# Sch_pwr_sys.net
KiCad netlist of a schematic drawn in Altium Designer
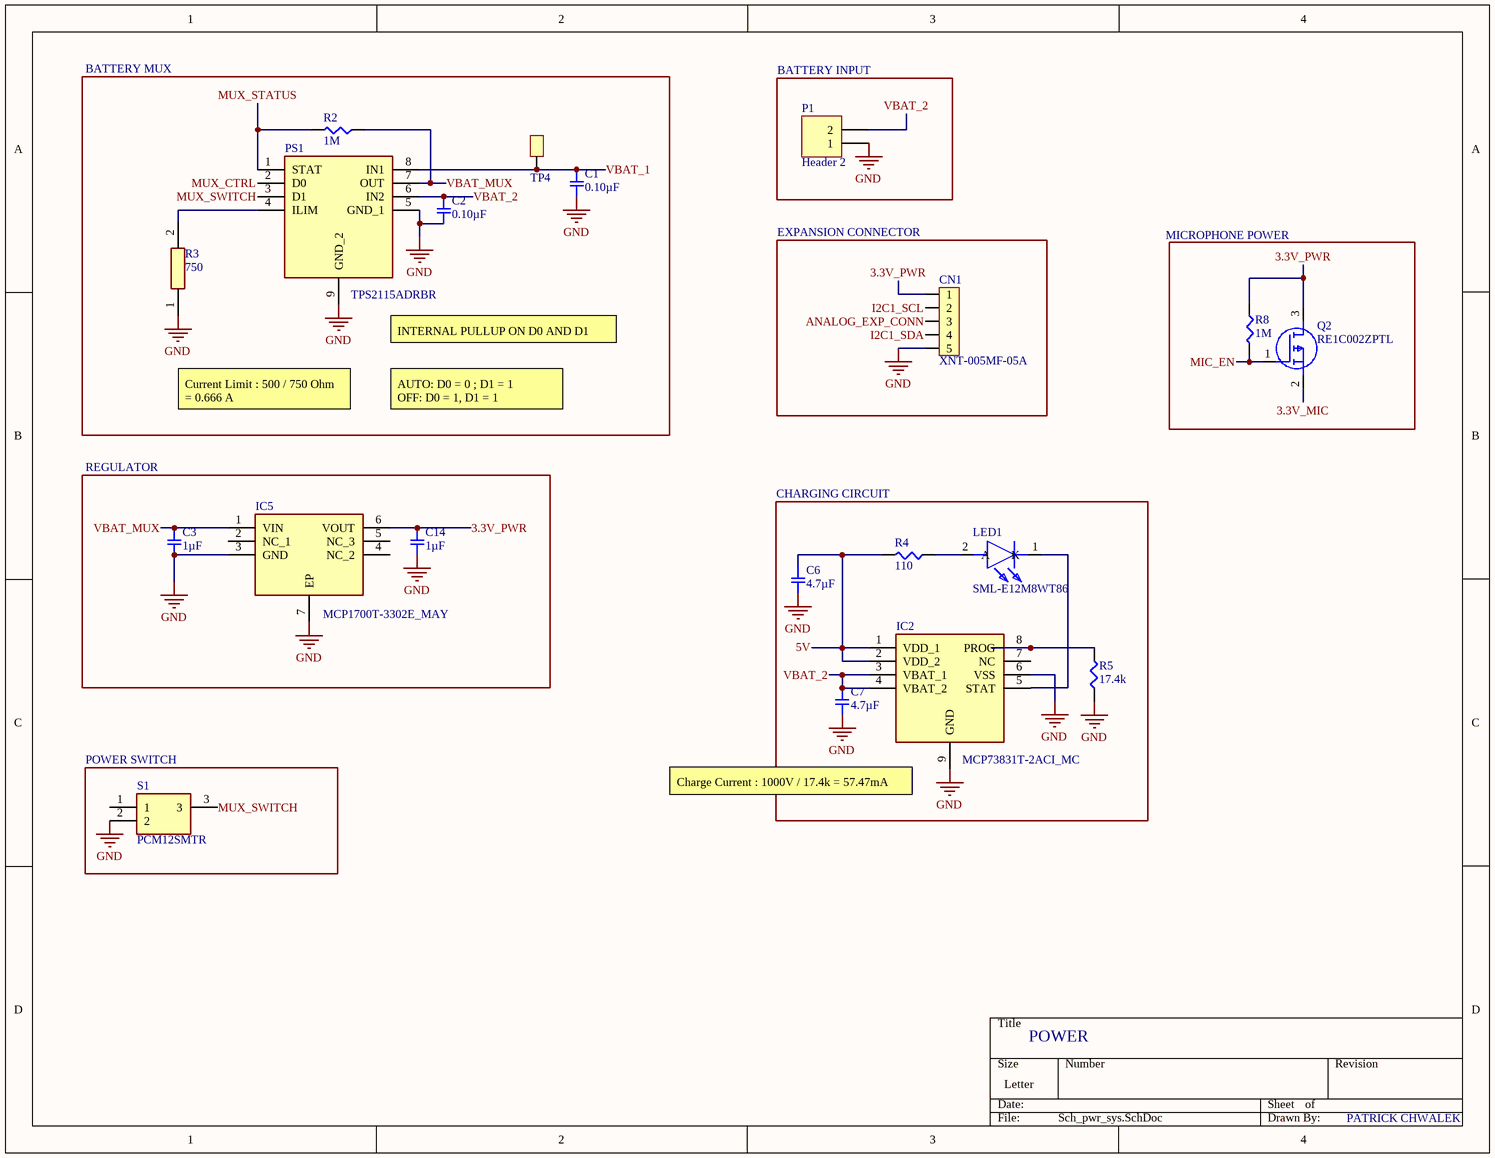
[diagram p0: Sch_pwr_sys.SchDoc]

(export (version "E")
  (design (tool "Eeschema 10.0.6"))
  (components
    (comp (ref "C1")
      (value "0.10µF")
      (footprint "SMD-0402C")
      (description "CAP CER 0.1UF 16V X7R 0402")
      (fields
        (field (name "DIGI-KEY PART NUMBER") "490-4759-1-ND")
        (field (name "PART NUMBER") "GCM155R71C104KA55D")
      )
      (libsource (lib "capacitor_murata_0402") (part "GCM155R71C104KA55D"))
    )
    (comp (ref "C2")
      (value "0.10µF")
      (footprint "SMD-0402C")
      (description "CAP CER 0.1UF 16V X7R 0402")
      (fields
        (field (name "DIGI-KEY PART NUMBER") "490-4759-1-ND")
        (field (name "PART NUMBER") "GCM155R71C104KA55D")
      )
      (libsource (lib "capacitor_murata_0402") (part "GCM155R71C104KA55D"))
    )
    (comp (ref "C3")
      (value "1µF")
      (footprint "SMD-0402C")
      (description "CAP CER 1UF 10V X7S 0402")
      (fields
        (field (name "DIGI-KEY PART NUMBER") "490-13409-1-ND")
        (field (name "PART NUMBER") "GCM155C71A105KE38D")
      )
      (libsource (lib "capacitor_murata_0402") (part "GCM155C71A105KE38D"))
    )
    (comp (ref "C6")
      (value "4.7µF")
      (footprint "SMD-0402C")
      (description "CAP CER 4.7UF 4V X5R 0402")
      (fields
        (field (name "DIGI-KEY PART NUMBER") "490-13231-1-ND")
        (field (name "PART NUMBER") "GRM153R60G475ME15D")
      )
      (libsource (lib "capacitor_murata_0402") (part "GRM153R60G475ME15D"))
    )
    (comp (ref "C7")
      (value "4.7µF")
      (footprint "SMD-0402C")
      (description "CAP CER 4.7UF 4V X5R 0402")
      (fields
        (field (name "DIGI-KEY PART NUMBER") "490-13231-1-ND")
        (field (name "PART NUMBER") "GRM153R60G475ME15D")
      )
      (libsource (lib "capacitor_murata_0402") (part "GRM153R60G475ME15D"))
    )
    (comp (ref "C14")
      (value "1µF")
      (footprint "SMD-0402C")
      (description "CAP CER 1UF 10V X7S 0402")
      (fields
        (field (name "DIGI-KEY PART NUMBER") "490-13409-1-ND")
        (field (name "PART NUMBER") "GCM155C71A105KE38D")
      )
      (libsource (lib "capacitor_murata_0402") (part "GCM155C71A105KE38D"))
    )
    (comp (ref "CN1")
      (value "XNT-005MF-05A")
      (footprint "XNT-005MF-05A")
      (libsource (lib "schematic_components") (part "XNT-005MF-05A"))
    )
    (comp (ref "IC2")
      (value "MCP73831T-2ACI_MC")
      (footprint "SamacSys:SON50P300X200X100-9N-D")
      (description "Integrated Circuit")
      (fields
        (field (name "MANUFACTURER_PART_NUMBER") "MCP73831T-2ACI/MC")
        (field (name "MOUSER PART NUMBER") "579-MCP73831T-2ACIMC")
      )
      (libsource (lib "*") (part "MCP73831T-2ACI_MC"))
    )
    (comp (ref "IC5")
      (value "MCP1700T-3302E_MAY")
      (footprint "SamacSys:SON65P200X200X90-7N")
      (description "Integrated Circuit")
      (fields
        (field (name "MANUFACTURER_PART_NUMBER") "MCP1700T-3302E/MAY")
        (field (name "MOUSER PART NUMBER") "579-MCP1700T3302EMAY")
      )
      (libsource (lib "*") (part "MCP1700T-3302E_MAY"))
    )
    (comp (ref "LED1")
      (value "SML-E12M8WT86")
      (footprint "SamacSys:LEDC1608X46N")
      (description "LED")
      (fields
        (field (name "MOUSER PART NUMBER") "755-SML-E12M8WT86")
        (field (name "RS PART NUMBER") "6942799")
      )
      (libsource (lib "*") (part "SML-E12M8WT86"))
    )
    (comp (ref "P1")
      (value "Header 2")
      (footprint "HDR1X2")
      (description "Header, 2-Pin")
      (fields (field (name "PUBLISHER") "Altium Limited"))
      (libsource (lib "Miscellaneous Connectors") (part "Header 2"))
    )
    (comp (ref "PS1")
      (value "TPS2115ADRBR")
      (footprint "SamacSys:SON65P300X300X100-9N-D")
      (description "Power Supply")
      (fields (field (name "MOUSER PART NUMBER") "595-TPS2115ADRBR"))
      (libsource (lib "*") (part "TPS2115ADRBR"))
    )
    (comp (ref "Q2")
      (value "RE1C002ZPTL")
      (footprint "SamacSys:SOTFL50P160X85-3N")
      (description "MOSFET (P-Channel)")
      (fields
        (field (name "MOUSER PART NUMBER") "755-RE1C002ZPTL")
        (field (name "RS PART NUMBER") "1486960P")
      )
      (libsource (lib "*") (part "RE1C002ZPTL"))
    )
    (comp (ref "R2")
      (value "1M")
      (footprint "SMD-0402-RES")
      (description "RES SMD 1M OHM 5% 1/10W 0402")
      (fields (field (name "PART NUMBER") "ERJ-2GEJ105X") (field (name "DIGI-KEY PART NUMBER") "P1.0MJCT-ND"))
      (libsource (lib "Panasonic_ERJ_0402") (part "ERJ-2GEJ105X"))
    )
    (comp (ref "R3")
      (value "750")
      (footprint "SamacSys:RESC1005X40N")
      (description "RES SMD 750 OHM 1% 1/10W 0402")
      (fields
        (field (name "MANUFACTURER_PART_NUMBER") "ERJ-2RKF7500X")
        (field (name "MOUSER PART NUMBER") "667-ERJ-2RKF7500X")
      )
      (libsource (lib "*") (part "ERJ-2RKF7500X"))
    )
    (comp (ref "R4")
      (value "110")
      (footprint "SMD-0402-RES")
      (description "RES SMD 110 OHM 5% 1/10W 0402")
      (fields
        (field (name "PART NUMBER") "ERJ-2RKF8062X")
        (field (name "DIGI-KEY PART NUMBER") "P80.6KLCT-ND")
      )
      (libsource (lib "Panasonic_ERJ_0402") (part "ERJ-2RKF8062X"))
    )
    (comp (ref "R5")
      (value "17.4k")
      (footprint "SMD-0402-RES")
      (description "RES SMD 17.4K OHM 1% 1/10W 0402")
      (fields (field (name "PART NUMBER") "ERJ-2GEJ103X") (field (name "DIGI-KEY PART NUMBER") "P10KJCT-ND"))
      (libsource (lib "Panasonic_ERJ_0402") (part "ERJ-2GEJ103X"))
    )
    (comp (ref "R8")
      (value "1M")
      (footprint "SMD-0402-RES")
      (description "RES SMD 1M OHM 5% 1/10W 0402")
      (fields (field (name "PART NUMBER") "ERJ-2GEJ105X") (field (name "DIGI-KEY PART NUMBER") "P1.0MJCT-ND"))
      (libsource (lib "Panasonic_ERJ_0402") (part "ERJ-2GEJ105X"))
    )
    (comp (ref "S1")
      (value "PCM12SMTR")
      (footprint "SamacSys:PCM12SMTR_1")
      (description "Switch")
      (fields (field (name "MOUSER PART NUMBER") "611-PCM12SMTR") (field (name "RS PART NUMBER") "7931721P"))
      (libsource (lib "*") (part "PCM12SMTR"))
    )
    (comp (ref "TP4")
      (value "TestPoint")
      (footprint "TestPoint_0.4mm")
      (libsource (lib "schematic_components") (part "TestPoint"))
    )
  )
  (nets
    (net (code "1") (name "/3.3V_MIC") (class "Default")
      (node (ref "Q2") (pin "2") (pinfunction "S_2") (pintype "passive"))
    )
    (net (code "2") (name "/3.3V_PWR") (class "Default")
      (node (ref "C14") (pin "1") (pinfunction "1_1") (pintype "passive"))
      (node (ref "CN1") (pin "1") (pinfunction "1_1") (pintype "passive"))
      (node (ref "IC5") (pin "6") (pinfunction "VOUT_6") (pintype "passive"))
      (node (ref "Q2") (pin "3") (pinfunction "D_3") (pintype "passive"))
      (node (ref "R8") (pin "1") (pinfunction "1_1") (pintype "passive"))
    )
    (net (code "3") (name "/5V") (class "Default")
      (node (ref "C6") (pin "1") (pinfunction "1_1") (pintype "passive"))
      (node (ref "IC2") (pin "1") (pinfunction "VDD_1_1") (pintype "passive"))
      (node (ref "IC2") (pin "2") (pinfunction "VDD_2_2") (pintype "passive"))
      (node (ref "R4") (pin "2") (pinfunction "2_2") (pintype "passive"))
    )
    (net (code "4") (name "/ANALOG_EXP_CONN") (class "Default")
      (node (ref "CN1") (pin "3") (pinfunction "3_3") (pintype "passive"))
    )
    (net (code "5") (name "/I2C1_SCL") (class "Default")
      (node (ref "CN1") (pin "2") (pinfunction "2_2") (pintype "passive"))
    )
    (net (code "6") (name "/I2C1_SDA") (class "Default")
      (node (ref "CN1") (pin "4") (pinfunction "4_4") (pintype "passive"))
    )
    (net (code "7") (name "/MIC_EN") (class "Default")
      (node (ref "Q2") (pin "1") (pinfunction "G_1") (pintype "passive"))
      (node (ref "R8") (pin "2") (pinfunction "2_2") (pintype "passive"))
    )
    (net (code "8") (name "/MUX_CTRL") (class "Default")
      (node (ref "PS1") (pin "2") (pinfunction "D0_2") (pintype "passive"))
    )
    (net (code "9") (name "/MUX_STATUS") (class "Default")
      (node (ref "PS1") (pin "1") (pinfunction "STAT_1") (pintype "passive"))
      (node (ref "R2") (pin "2") (pinfunction "2_2") (pintype "passive"))
    )
    (net (code "10") (name "/MUX_SWITCH") (class "Default")
      (node (ref "PS1") (pin "3") (pinfunction "D1_3") (pintype "passive"))
      (node (ref "S1") (pin "3") (pinfunction "3_3") (pintype "passive"))
    )
    (net (code "11") (name "/VBAT_1") (class "Default")
      (node (ref "C1") (pin "1") (pinfunction "1_1") (pintype "passive"))
      (node (ref "PS1") (pin "8") (pinfunction "IN1_8") (pintype "passive"))
      (node (ref "TP4") (pin "1") (pinfunction "1_1") (pintype "passive"))
    )
    (net (code "12") (name "/VBAT_2") (class "Default")
      (node (ref "C2") (pin "1") (pinfunction "1_1") (pintype "passive"))
      (node (ref "C7") (pin "1") (pinfunction "1_1") (pintype "passive"))
      (node (ref "IC2") (pin "3") (pinfunction "VBAT_1_3") (pintype "passive"))
      (node (ref "IC2") (pin "4") (pinfunction "VBAT_2_4") (pintype "passive"))
      (node (ref "P1") (pin "2") (pinfunction "2_2") (pintype "passive"))
      (node (ref "PS1") (pin "6") (pinfunction "IN2_6") (pintype "passive"))
    )
    (net (code "13") (name "/VBAT_MUX") (class "Default")
      (node (ref "C3") (pin "1") (pinfunction "1_1") (pintype "passive"))
      (node (ref "IC5") (pin "1") (pinfunction "VIN_1") (pintype "passive"))
      (node (ref "PS1") (pin "7") (pinfunction "OUT_7") (pintype "passive"))
      (node (ref "R2") (pin "1") (pinfunction "1_1") (pintype "passive"))
    )
    (net (code "14") (name "GND") (class "Default")
      (node (ref "C1") (pin "2") (pinfunction "2_2") (pintype "passive"))
      (node (ref "C14") (pin "2") (pinfunction "2_2") (pintype "passive"))
      (node (ref "C2") (pin "2") (pinfunction "2_2") (pintype "passive"))
      (node (ref "C3") (pin "2") (pinfunction "2_2") (pintype "passive"))
      (node (ref "C6") (pin "2") (pinfunction "2_2") (pintype "passive"))
      (node (ref "C7") (pin "2") (pinfunction "2_2") (pintype "passive"))
      (node (ref "CN1") (pin "5") (pinfunction "5_5") (pintype "passive"))
      (node (ref "IC2") (pin "6") (pinfunction "VSS_6") (pintype "passive"))
      (node (ref "IC2") (pin "9") (pinfunction "GND_9") (pintype "passive"))
      (node (ref "IC5") (pin "3") (pinfunction "GND_3") (pintype "passive"))
      (node (ref "IC5") (pin "7") (pinfunction "EP_7") (pintype "passive"))
      (node (ref "P1") (pin "1") (pinfunction "1_1") (pintype "passive"))
      (node (ref "PS1") (pin "5") (pinfunction "GND_1_5") (pintype "passive"))
      (node (ref "PS1") (pin "9") (pinfunction "GND_2_9") (pintype "passive"))
      (node (ref "R3") (pin "1") (pinfunction "1_1") (pintype "passive"))
      (node (ref "R5") (pin "1") (pinfunction "1_1") (pintype "passive"))
      (node (ref "S1") (pin "2") (pinfunction "2_2") (pintype "passive"))
    )
    (net (code "15") (name "Net-(IC2-PROG)") (class "Default")
      (node (ref "IC2") (pin "8") (pinfunction "PROG_8") (pintype "passive"))
      (node (ref "R5") (pin "2") (pinfunction "2_2") (pintype "passive"))
    )
    (net (code "16") (name "Net-(IC2-STAT)") (class "Default")
      (node (ref "IC2") (pin "5") (pinfunction "STAT_5") (pintype "passive"))
      (node (ref "LED1") (pin "1") (pinfunction "K_1") (pintype "passive"))
    )
    (net (code "17") (name "Net-(LED1-A)") (class "Default")
      (node (ref "LED1") (pin "2") (pinfunction "A_2") (pintype "passive"))
      (node (ref "R4") (pin "1") (pinfunction "1_1") (pintype "passive"))
    )
    (net (code "18") (name "Net-(PS1-ILIM)") (class "Default")
      (node (ref "PS1") (pin "4") (pinfunction "ILIM_4") (pintype "passive"))
      (node (ref "R3") (pin "2") (pinfunction "2_2") (pintype "passive"))
    )
    (net (code "19") (name "unconnected-(IC2-NC-Pad7)") (class "Default")
      (node (ref "IC2") (pin "7") (pinfunction "NC_7") (pintype "passive"))
    )
    (net (code "20") (name "unconnected-(IC5-NC_1-Pad2)") (class "Default")
      (node (ref "IC5") (pin "2") (pinfunction "NC_1_2") (pintype "passive"))
    )
    (net (code "21") (name "unconnected-(IC5-NC_2-Pad4)") (class "Default")
      (node (ref "IC5") (pin "4") (pinfunction "NC_2_4") (pintype "passive"))
    )
    (net (code "22") (name "unconnected-(IC5-NC_3-Pad5)") (class "Default")
      (node (ref "IC5") (pin "5") (pinfunction "NC_3_5") (pintype "passive"))
    )
    (net (code "23") (name "unconnected-(S1-Pad1)") (class "Default")
      (node (ref "S1") (pin "1") (pinfunction "1_1") (pintype "passive"))
    )
  )
)
